# Block_Diagram.net
KiCad netlist of a schematic drawn in Altium Designer
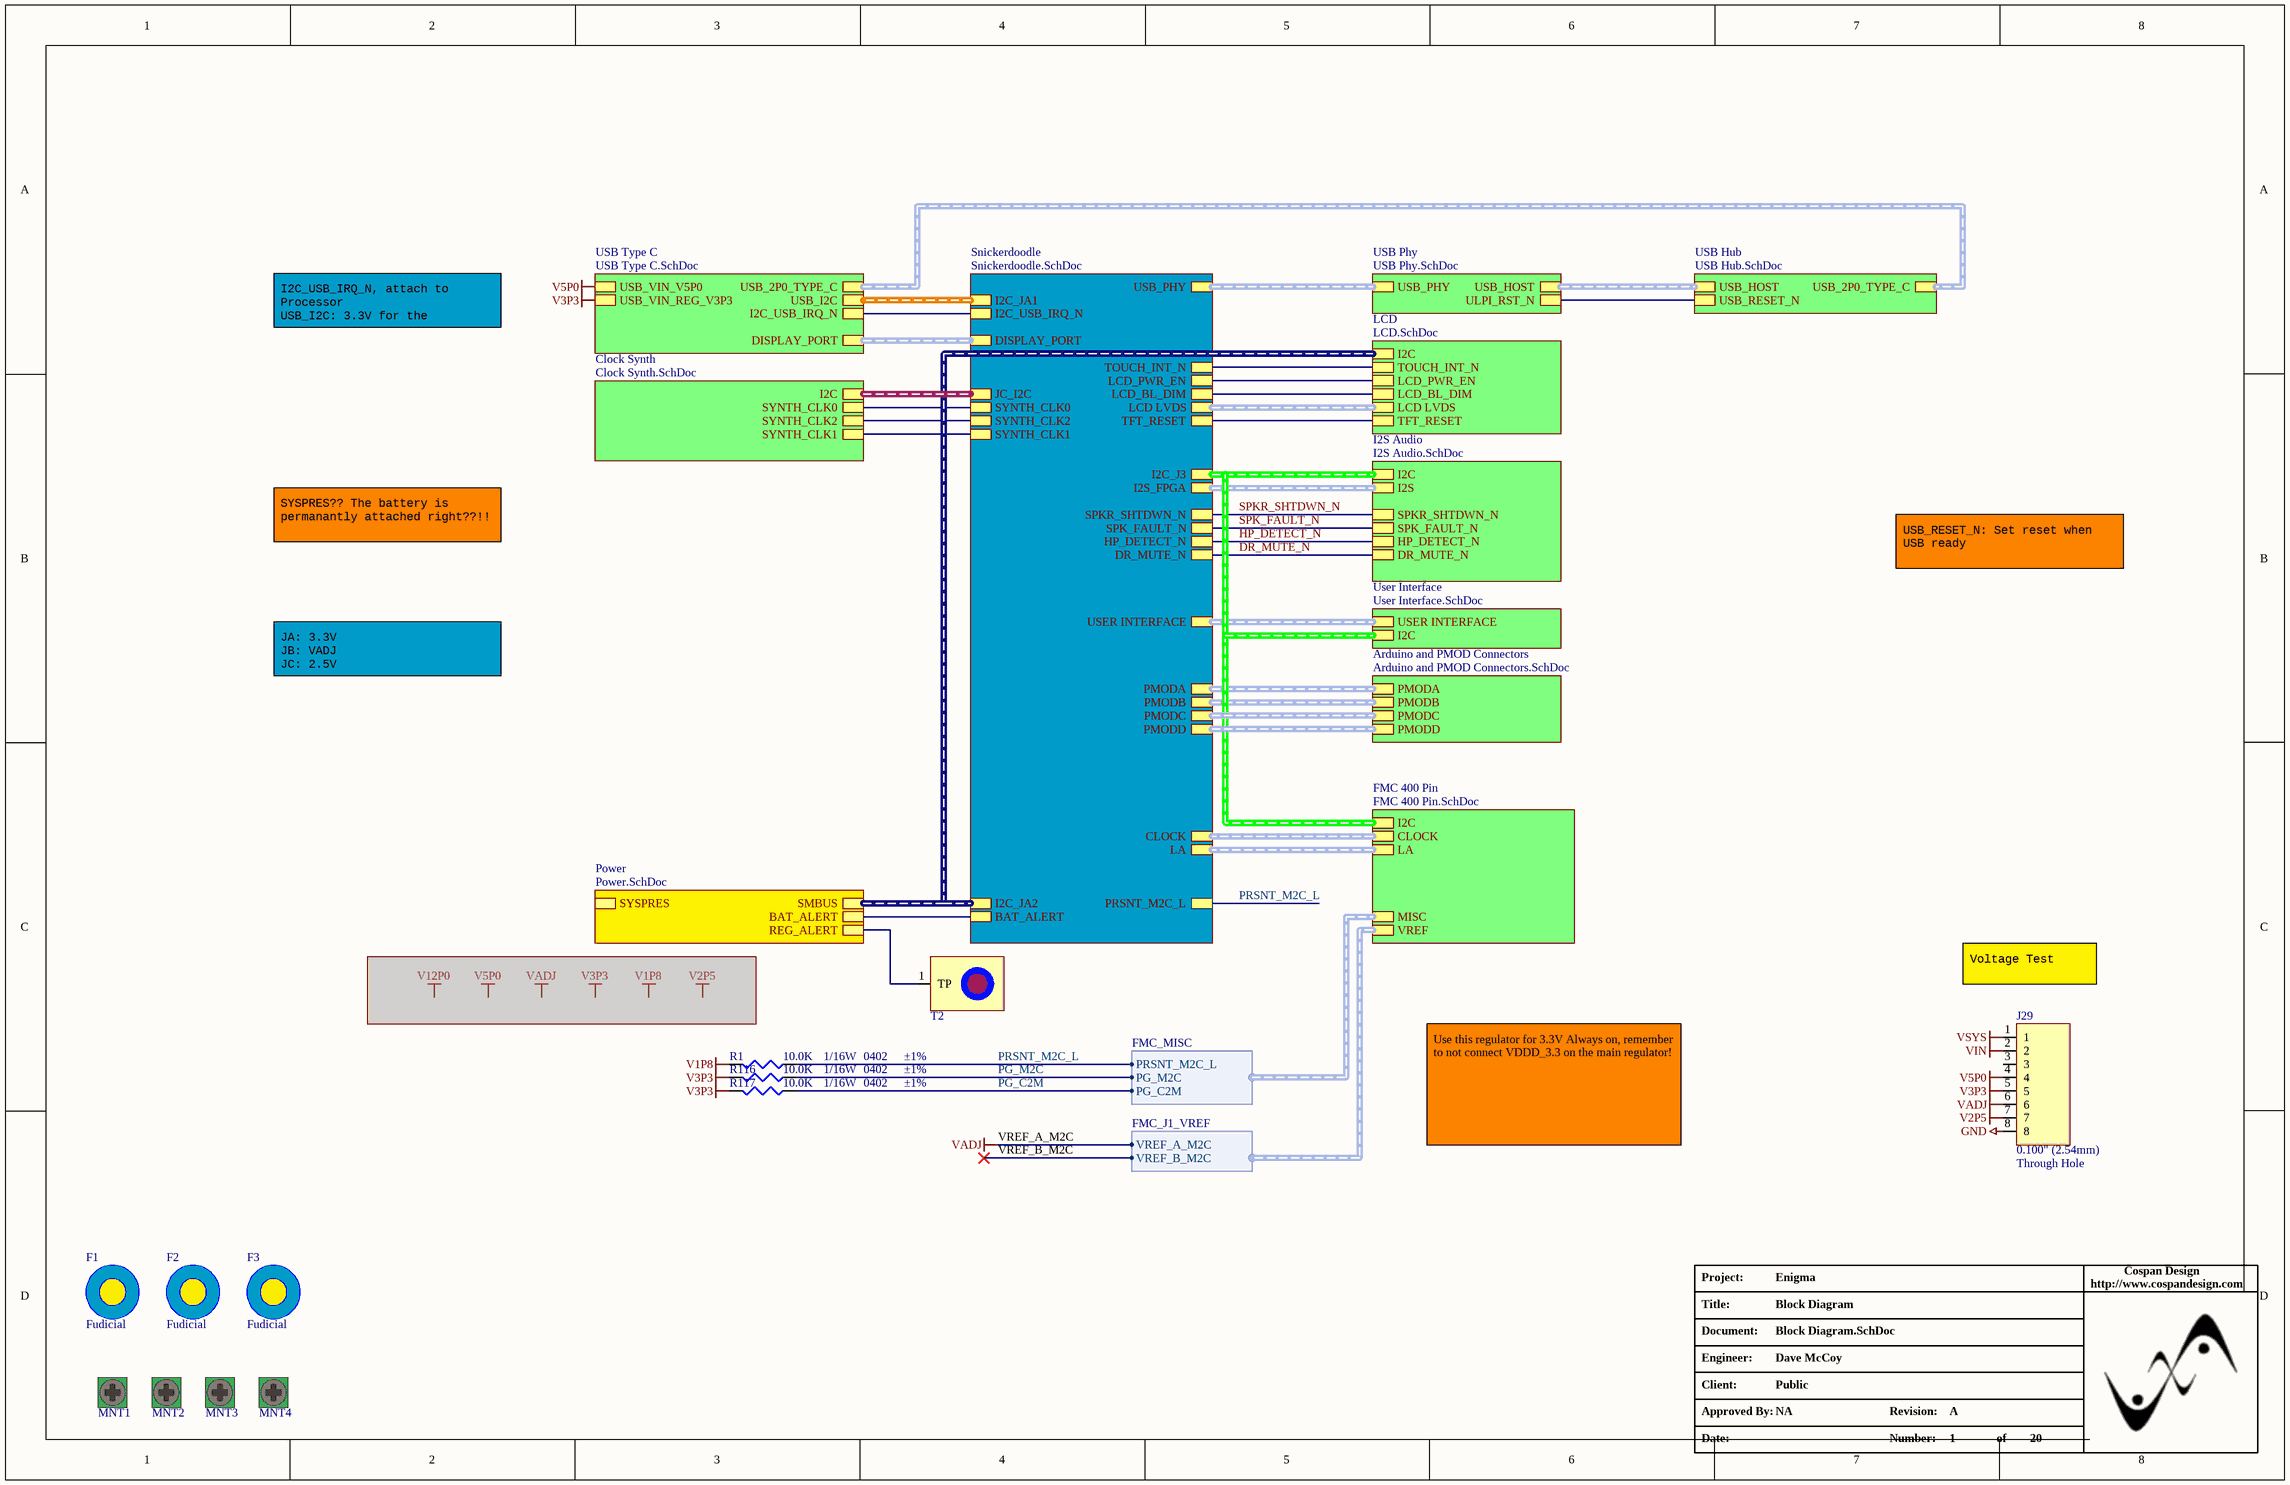
[diagram p0: Block Diagram.SchDoc]

(export (version "E")
  (design (tool "Eeschema 10.0.6"))
  (components
    (comp (ref "F1")
      (value "Fudicial")
      (footprint "FIDUCIAL ROUND")
      (libsource (lib "Main Library") (part "F_FUDICIAL"))
    )
    (comp (ref "F2")
      (value "Fudicial")
      (footprint "FIDUCIAL ROUND")
      (libsource (lib "Main Library") (part "F_FUDICIAL"))
    )
    (comp (ref "F3")
      (value "Fudicial")
      (footprint "FIDUCIAL ROUND")
      (libsource (lib "Main Library") (part "F_FUDICIAL"))
    )
    (comp (ref "J29")
      (value "J_HDR1X8_THRHOLE_VERT_RECPT")
      (footprint "HDR_1X8 - FEMALE")
      (description "CONN HEADER FEMALE 8POS .1\" TIN")
      (fields
        (field (name "MANUFACTURER") "Samtec")
        (field (name "MANUFACTURER PART NUMBER") "SSW-108-01-T-S")
        (field (name "PITCH") "0.100\" (2.54mm)")
        (field (name "MOUNTING TYPE") "Through Hole")
      )
      (libsource (lib "Main Library") (part "J_HDR1X8_THRHOLE_VERT_FEMALE"))
    )
    (comp (ref "MNT1")
      (value "Mounting Hole")
      (footprint "MNT_4-40")
      (libsource (lib "Main Library") (part "MNT_440_HOLE"))
    )
    (comp (ref "MNT2")
      (value "Mounting Hole")
      (footprint "MNT_4-40")
      (libsource (lib "Main Library") (part "MNT_440_HOLE"))
    )
    (comp (ref "MNT3")
      (value "Mounting Hole")
      (footprint "MNT_4-40")
      (libsource (lib "Main Library") (part "MNT_440_HOLE"))
    )
    (comp (ref "MNT4")
      (value "Mounting Hole")
      (footprint "MNT_4-40")
      (libsource (lib "Main Library") (part "MNT_440_HOLE"))
    )
    (comp (ref "R1")
      (value "R_0402_10.0K")
      (footprint "R_0402")
      (description "RES 10.0K OHM 1/16W 1% 0402 SMD")
      (fields
        (field (name "MANUFACTURER") "Stackpole Electronics Inc")
        (field (name "MANUFACTURER PART NUMBER") "RMCF0402FT10K0")
        (field (name "RESISTANCE IN OHMS") "10.0K")
        (field (name "POWER (WATTS)") "1/16W")
        (field (name "CASE") "0402")
        (field (name "TOLERANCE") "±1%")
      )
      (libsource (lib "Cospan Design") (part "R_0402_10.0K"))
    )
    (comp (ref "R116")
      (value "R_0402_10.0K")
      (footprint "R_0402")
      (description "RES 10.0K OHM 1/16W 1% 0402 SMD")
      (fields
        (field (name "MANUFACTURER") "Stackpole Electronics Inc")
        (field (name "MANUFACTURER PART NUMBER") "RMCF0402FT10K0")
        (field (name "RESISTANCE IN OHMS") "10.0K")
        (field (name "POWER (WATTS)") "1/16W")
        (field (name "CASE") "0402")
        (field (name "TOLERANCE") "±1%")
      )
      (libsource (lib "Cospan Design") (part "R_0402_10.0K"))
    )
    (comp (ref "R117")
      (value "R_0402_10.0K")
      (footprint "R_0402")
      (description "RES 10.0K OHM 1/16W 1% 0402 SMD")
      (fields
        (field (name "MANUFACTURER") "Stackpole Electronics Inc")
        (field (name "MANUFACTURER PART NUMBER") "RMCF0402FT10K0")
        (field (name "RESISTANCE IN OHMS") "10.0K")
        (field (name "POWER (WATTS)") "1/16W")
        (field (name "CASE") "0402")
        (field (name "TOLERANCE") "±1%")
      )
      (libsource (lib "Cospan Design") (part "R_0402_10.0K"))
    )
    (comp (ref "T2")
      (value "TEST_POINT_SMALL")
      (footprint "TestPointSmall")
      (description "OSCILLOSCOPE TEST POINT")
      (libsource (lib "Main Library") (part "TEST_POINT_SMALL"))
    )
  )
  (nets
    (net (code "18") (name "/PG_C2M") (class "Default")
      (node (ref "R117") (pin "2") (pinfunction "2_2") (pintype "passive"))
    )
    (net (code "19") (name "/PG_M2C") (class "Default")
      (node (ref "R116") (pin "2") (pinfunction "2_2") (pintype "passive"))
    )
    (net (code "24") (name "/PRSNT_M2C_L") (class "Default")
      (node (ref "R1") (pin "2") (pinfunction "2_2") (pintype "passive"))
    )
    (net (code "25") (name "/REG_ALERT") (class "Default")
      (node (ref "T2") (pin "1") (pinfunction "TP_1") (pintype "passive"))
    )
    (net (code "42") (name "GND") (class "Default")
      (node (ref "J29") (pin "8") (pinfunction "8_8") (pintype "passive"))
    )
    (net (code "43") (name "V1P8") (class "Default")
      (node (ref "R1") (pin "1") (pinfunction "1_1") (pintype "passive"))
    )
    (net (code "44") (name "V2P5") (class "Default")
      (node (ref "J29") (pin "7") (pinfunction "7_7") (pintype "passive"))
    )
    (net (code "45") (name "V3P3") (class "Default")
      (node (ref "J29") (pin "5") (pinfunction "5_5") (pintype "passive"))
      (node (ref "R116") (pin "1") (pinfunction "1_1") (pintype "passive"))
      (node (ref "R117") (pin "1") (pinfunction "1_1") (pintype "passive"))
    )
    (net (code "46") (name "V5P0") (class "Default")
      (node (ref "J29") (pin "4") (pinfunction "4_4") (pintype "passive"))
    )
    (net (code "48") (name "VADJ") (class "Default")
      (node (ref "J29") (pin "6") (pinfunction "6_6") (pintype "passive"))
    )
    (net (code "49") (name "VIN") (class "Default")
      (node (ref "J29") (pin "2") (pinfunction "2_2") (pintype "passive"))
    )
    (net (code "50") (name "VSYS") (class "Default")
      (node (ref "J29") (pin "1") (pinfunction "1_1") (pintype "passive"))
    )
    (net (code "51") (name "unconnected-(J29-Pad3)") (class "Default")
      (node (ref "J29") (pin "3") (pinfunction "3_3") (pintype "passive"))
    )
  )
)
